# Optoisolator.net
KiCad netlist of a schematic drawn in EAGLE
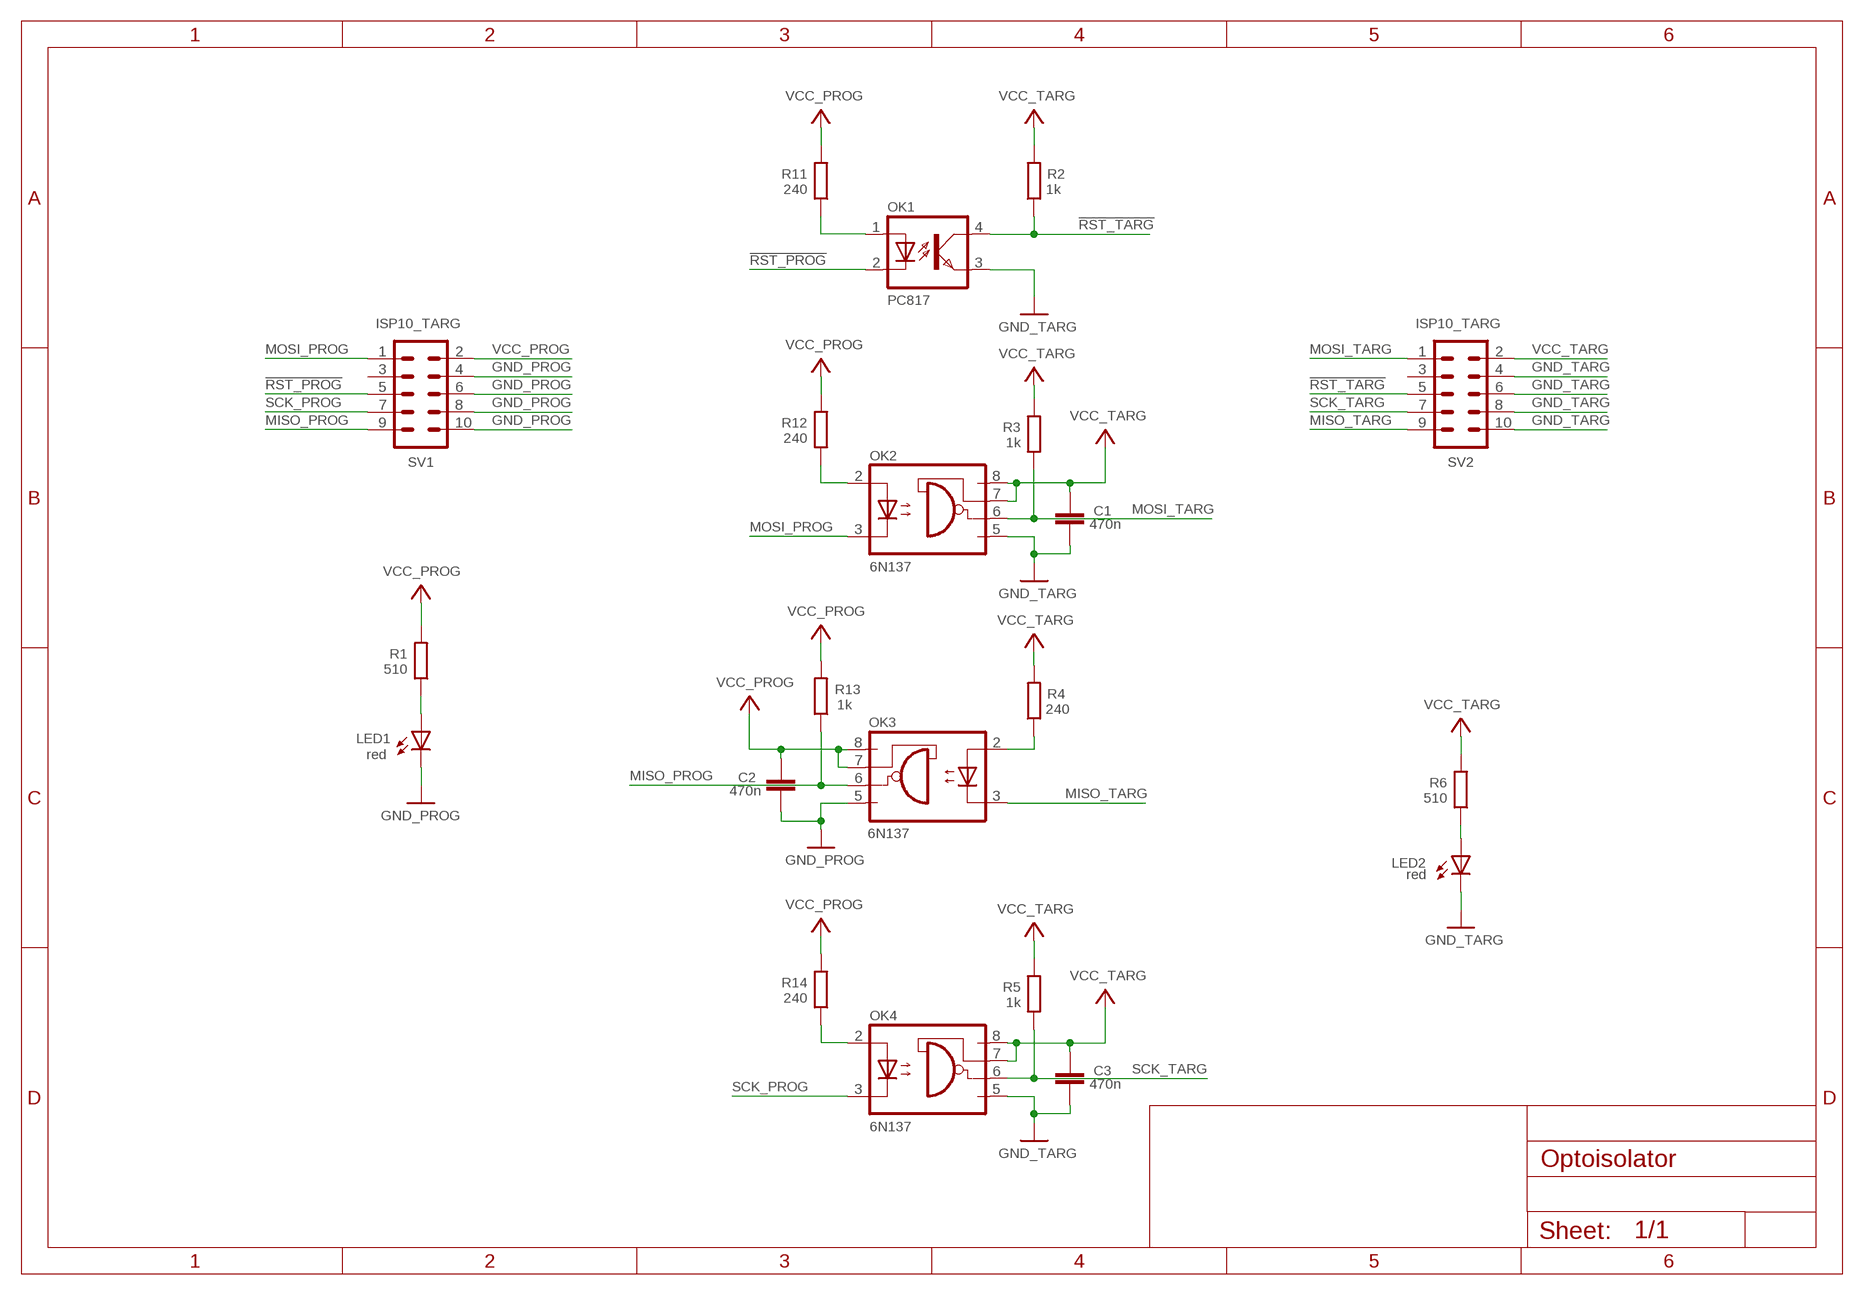
[diagram p0: schematic, sheet 1]

(export (version "E")
  (design (tool "Eeschema 10.0.6"))
  (components
    (comp (ref "C1")
      (value "470n")
      (footprint "eagle-import:C1206")
      (libsource (lib "eagle-import") (part "CAPC1206"))
    )
    (comp (ref "C2")
      (value "470n")
      (footprint "eagle-import:C1206")
      (libsource (lib "eagle-import") (part "CAPC1206"))
    )
    (comp (ref "C3")
      (value "470n")
      (footprint "eagle-import:C1206")
      (libsource (lib "eagle-import") (part "CAPC1206"))
    )
    (comp (ref "LED1")
      (value "red")
      (footprint "eagle-import:LED3MM")
      (libsource (lib "eagle-import") (part "LED3MM"))
    )
    (comp (ref "LED2")
      (value "red")
      (footprint "eagle-import:LED3MM")
      (libsource (lib "eagle-import") (part "LED3MM"))
    )
    (comp (ref "OK1")
      (value "PC817")
      (footprint "eagle-import:DIL04")
      (fields (field (name "MPN") "PC817X4J000F"))
      (libsource (lib "eagle-import") (part "PC817"))
    )
    (comp (ref "OK2")
      (value "6N137")
      (footprint "eagle-import:DIL08")
      (libsource (lib "eagle-import") (part "6N137"))
    )
    (comp (ref "OK3")
      (value "6N137")
      (footprint "eagle-import:DIL08")
      (libsource (lib "eagle-import") (part "6N137"))
    )
    (comp (ref "OK4")
      (value "6N137")
      (footprint "eagle-import:DIL08")
      (libsource (lib "eagle-import") (part "6N137"))
    )
    (comp (ref "R1")
      (value "510")
      (footprint "eagle-import:R1206")
      (libsource (lib "eagle-import") (part "RESR1206"))
    )
    (comp (ref "R2")
      (value "1k")
      (footprint "eagle-import:R1206")
      (libsource (lib "eagle-import") (part "RESR1206"))
    )
    (comp (ref "R3")
      (value "1k")
      (footprint "eagle-import:R1206")
      (libsource (lib "eagle-import") (part "RESR1206"))
    )
    (comp (ref "R4")
      (value "240")
      (footprint "eagle-import:R1206")
      (libsource (lib "eagle-import") (part "RESR1206"))
    )
    (comp (ref "R5")
      (value "1k")
      (footprint "eagle-import:R1206")
      (libsource (lib "eagle-import") (part "RESR1206"))
    )
    (comp (ref "R6")
      (value "510")
      (footprint "eagle-import:R1206")
      (libsource (lib "eagle-import") (part "RESR1206"))
    )
    (comp (ref "R11")
      (value "240")
      (footprint "eagle-import:R1206")
      (libsource (lib "eagle-import") (part "RESR1206"))
    )
    (comp (ref "R12")
      (value "240")
      (footprint "eagle-import:R1206")
      (libsource (lib "eagle-import") (part "RESR1206"))
    )
    (comp (ref "R13")
      (value "1k")
      (footprint "eagle-import:R1206")
      (libsource (lib "eagle-import") (part "RESR1206"))
    )
    (comp (ref "R14")
      (value "240")
      (footprint "eagle-import:R1206")
      (libsource (lib "eagle-import") (part "RESR1206"))
    )
    (comp (ref "SV1")
      (value "ISP10_TARG")
      (footprint "eagle-import:ML10")
      (fields (field (name "OC_FARNELL") "unknown") (field (name "OC_NEWARK") "unknown"))
      (libsource (lib "eagle-import") (part "ML10"))
    )
    (comp (ref "SV2")
      (value "ISP10_TARG")
      (footprint "eagle-import:ML10")
      (libsource (lib "eagle-import") (part "ML10"))
    )
  )
  (nets
    (net (code "1") (name "/MISO_PROG") (class "Default")
      (node (ref "OK3") (pin "6") (pinfunction "VO_6") (pintype "passive"))
      (node (ref "R13") (pin "1") (pinfunction "1_1") (pintype "passive"))
      (node (ref "SV1") (pin "9") (pinfunction "9_9") (pintype "passive"))
    )
    (net (code "2") (name "/MISO_TARG") (class "Default")
      (node (ref "OK3") (pin "3") (pinfunction "C_3") (pintype "passive"))
      (node (ref "SV2") (pin "9") (pinfunction "9_9") (pintype "passive"))
    )
    (net (code "3") (name "/MOSI_PROG") (class "Default")
      (node (ref "OK2") (pin "3") (pinfunction "C_3") (pintype "passive"))
      (node (ref "SV1") (pin "1") (pinfunction "1_1") (pintype "passive"))
    )
    (net (code "4") (name "/MOSI_TARG") (class "Default")
      (node (ref "OK2") (pin "6") (pinfunction "VO_6") (pintype "passive"))
      (node (ref "R3") (pin "1") (pinfunction "1_1") (pintype "passive"))
      (node (ref "SV2") (pin "1") (pinfunction "1_1") (pintype "passive"))
    )
    (net (code "5") (name "/SCK_PROG") (class "Default")
      (node (ref "OK4") (pin "3") (pinfunction "C_3") (pintype "passive"))
      (node (ref "SV1") (pin "7") (pinfunction "7_7") (pintype "passive"))
    )
    (net (code "6") (name "/SCK_TARG") (class "Default")
      (node (ref "OK4") (pin "6") (pinfunction "VO_6") (pintype "passive"))
      (node (ref "R5") (pin "1") (pinfunction "1_1") (pintype "passive"))
      (node (ref "SV2") (pin "7") (pinfunction "7_7") (pintype "passive"))
    )
    (net (code "7") (name "/~{RST_PROG}") (class "Default")
      (node (ref "OK1") (pin "2") (pinfunction "C_2") (pintype "passive"))
      (node (ref "SV1") (pin "5") (pinfunction "5_5") (pintype "passive"))
    )
    (net (code "8") (name "/~{RST_TARG}") (class "Default")
      (node (ref "OK1") (pin "4") (pinfunction "COL_4") (pintype "passive"))
      (node (ref "R2") (pin "1") (pinfunction "1_1") (pintype "passive"))
      (node (ref "SV2") (pin "5") (pinfunction "5_5") (pintype "passive"))
    )
    (net (code "9") (name "GND_PROG") (class "Default")
      (node (ref "C2") (pin "2") (pinfunction "2_2") (pintype "passive"))
      (node (ref "LED1") (pin "K") (pinfunction "C_K") (pintype "passive"))
      (node (ref "OK3") (pin "5") (pinfunction "GND_5") (pintype "passive"))
      (node (ref "SV1") (pin "10") (pinfunction "10_10") (pintype "passive"))
      (node (ref "SV1") (pin "4") (pinfunction "4_4") (pintype "passive"))
      (node (ref "SV1") (pin "6") (pinfunction "6_6") (pintype "passive"))
      (node (ref "SV1") (pin "8") (pinfunction "8_8") (pintype "passive"))
    )
    (net (code "10") (name "GND_TARG") (class "Default")
      (node (ref "C1") (pin "2") (pinfunction "2_2") (pintype "passive"))
      (node (ref "C3") (pin "2") (pinfunction "2_2") (pintype "passive"))
      (node (ref "LED2") (pin "K") (pinfunction "C_K") (pintype "passive"))
      (node (ref "OK1") (pin "3") (pinfunction "EMIT_3") (pintype "passive"))
      (node (ref "OK2") (pin "5") (pinfunction "GND_5") (pintype "passive"))
      (node (ref "OK4") (pin "5") (pinfunction "GND_5") (pintype "passive"))
      (node (ref "SV2") (pin "10") (pinfunction "10_10") (pintype "passive"))
      (node (ref "SV2") (pin "4") (pinfunction "4_4") (pintype "passive"))
      (node (ref "SV2") (pin "6") (pinfunction "6_6") (pintype "passive"))
      (node (ref "SV2") (pin "8") (pinfunction "8_8") (pintype "passive"))
    )
    (net (code "11") (name "Net-(LED1-PadA)") (class "Default")
      (node (ref "LED1") (pin "A") (pinfunction "A_A") (pintype "passive"))
      (node (ref "R1") (pin "1") (pinfunction "1_1") (pintype "passive"))
    )
    (net (code "12") (name "Net-(LED2-PadA)") (class "Default")
      (node (ref "LED2") (pin "A") (pinfunction "A_A") (pintype "passive"))
      (node (ref "R6") (pin "1") (pinfunction "1_1") (pintype "passive"))
    )
    (net (code "13") (name "Net-(OK1-A)") (class "Default")
      (node (ref "OK1") (pin "1") (pinfunction "A_1") (pintype "passive"))
      (node (ref "R11") (pin "1") (pinfunction "1_1") (pintype "passive"))
    )
    (net (code "14") (name "Net-(OK2-A)") (class "Default")
      (node (ref "OK2") (pin "2") (pinfunction "A_2") (pintype "passive"))
      (node (ref "R12") (pin "1") (pinfunction "1_1") (pintype "passive"))
    )
    (net (code "15") (name "Net-(OK3-A)") (class "Default")
      (node (ref "OK3") (pin "2") (pinfunction "A_2") (pintype "passive"))
      (node (ref "R4") (pin "1") (pinfunction "1_1") (pintype "passive"))
    )
    (net (code "16") (name "Net-(OK4-A)") (class "Default")
      (node (ref "OK4") (pin "2") (pinfunction "A_2") (pintype "passive"))
      (node (ref "R14") (pin "1") (pinfunction "1_1") (pintype "passive"))
    )
    (net (code "17") (name "VCC_PROG") (class "Default")
      (node (ref "C2") (pin "1") (pinfunction "1_1") (pintype "passive"))
      (node (ref "OK3") (pin "7") (pinfunction "VE_7") (pintype "passive"))
      (node (ref "OK3") (pin "8") (pinfunction "VCC_8") (pintype "passive"))
      (node (ref "R1") (pin "2") (pinfunction "2_2") (pintype "passive"))
      (node (ref "R11") (pin "2") (pinfunction "2_2") (pintype "passive"))
      (node (ref "R12") (pin "2") (pinfunction "2_2") (pintype "passive"))
      (node (ref "R13") (pin "2") (pinfunction "2_2") (pintype "passive"))
      (node (ref "R14") (pin "2") (pinfunction "2_2") (pintype "passive"))
      (node (ref "SV1") (pin "2") (pinfunction "2_2") (pintype "passive"))
    )
    (net (code "18") (name "VCC_TARG") (class "Default")
      (node (ref "C1") (pin "1") (pinfunction "1_1") (pintype "passive"))
      (node (ref "C3") (pin "1") (pinfunction "1_1") (pintype "passive"))
      (node (ref "OK2") (pin "7") (pinfunction "VE_7") (pintype "passive"))
      (node (ref "OK2") (pin "8") (pinfunction "VCC_8") (pintype "passive"))
      (node (ref "OK4") (pin "7") (pinfunction "VE_7") (pintype "passive"))
      (node (ref "OK4") (pin "8") (pinfunction "VCC_8") (pintype "passive"))
      (node (ref "R2") (pin "2") (pinfunction "2_2") (pintype "passive"))
      (node (ref "R3") (pin "2") (pinfunction "2_2") (pintype "passive"))
      (node (ref "R4") (pin "2") (pinfunction "2_2") (pintype "passive"))
      (node (ref "R5") (pin "2") (pinfunction "2_2") (pintype "passive"))
      (node (ref "R6") (pin "2") (pinfunction "2_2") (pintype "passive"))
      (node (ref "SV2") (pin "2") (pinfunction "2_2") (pintype "passive"))
    )
    (net (code "19") (name "unconnected-(SV1-Pad3)") (class "Default")
      (node (ref "SV1") (pin "3") (pinfunction "3_3") (pintype "passive"))
    )
    (net (code "20") (name "unconnected-(SV2-Pad3)") (class "Default")
      (node (ref "SV2") (pin "3") (pinfunction "3_3") (pintype "passive"))
    )
  )
)
